# c50.net
KiCad netlist of a schematic drawn in EAGLE
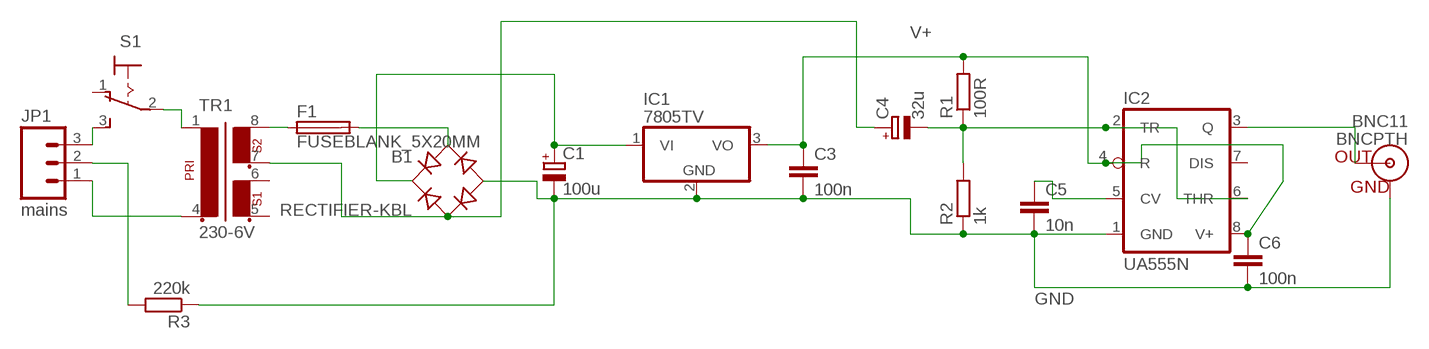
[diagram p0: schematic, sheet 1]

(export (version "E")
  (design (tool "Eeschema 10.0.6"))
  (components
    (comp (ref "B1")
      (value "RECTIFIER-KBL")
      (footprint "eagle-import:B-DIL")
      (libsource (lib "eagle-import") (part "B-DIL"))
    )
    (comp (ref "BNC11")
      (value "BNCPTH")
      (footprint "eagle-import:BNC")
      (libsource (lib "eagle-import") (part "BNCPTH"))
    )
    (comp (ref "C1")
      (value "100u")
      (footprint "eagle-import:E2,5-7")
      (libsource (lib "eagle-import") (part "CPOL-EUE2.5-7"))
    )
    (comp (ref "C3")
      (value "100n")
      (footprint "eagle-import:C050-024X044")
      (libsource (lib "eagle-import") (part "C-EU050-024X044"))
    )
    (comp (ref "C4")
      (value "32u")
      (footprint "eagle-import:E5-13")
      (libsource (lib "eagle-import") (part "CPOL-EUE5-13"))
    )
    (comp (ref "C5")
      (value "10n")
      (footprint "eagle-import:C050-024X044")
      (libsource (lib "eagle-import") (part "C-EU050-024X044"))
    )
    (comp (ref "C6")
      (value "100n")
      (footprint "eagle-import:C050-024X044")
      (libsource (lib "eagle-import") (part "C-EU050-024X044"))
    )
    (comp (ref "F1")
      (value "FUSEBLANK_5X20MM")
      (footprint "eagle-import:FUSE_HOLDER_5X20MM")
      (libsource (lib "eagle-import") (part "FUSEBLANK_5X20MM"))
    )
    (comp (ref "IC1")
      (value "7805TV")
      (footprint "eagle-import:TO220V")
      (libsource (lib "eagle-import") (part "78TV05"))
    )
    (comp (ref "IC2")
      (value "UA555N")
      (footprint "eagle-import:DIL08")
      (libsource (lib "eagle-import") (part "555NUA"))
    )
    (comp (ref "JP1")
      (value "mains")
      (footprint "eagle-import:SCREWTERMINAL-5MM-3")
      (libsource (lib "eagle-import") (part "M03-SCREW-5MM"))
    )
    (comp (ref "R1")
      (value "100R")
      (footprint "eagle-import:0207_10")
      (libsource (lib "eagle-import") (part "R-EU_0207/10"))
    )
    (comp (ref "R2")
      (value "1k")
      (footprint "eagle-import:0207_10")
      (libsource (lib "eagle-import") (part "R-EU_0207/10"))
    )
    (comp (ref "R3")
      (value "220k")
      (footprint "eagle-import:0207_10")
      (libsource (lib "eagle-import") (part "R-EU_0207/10"))
    )
    (comp (ref "S1")
      (value "320-916")
      (footprint "eagle-import:320-916")
      (libsource (lib "eagle-import") (part "320-916"))
    )
    (comp (ref "TR1")
      (value "230-6V")
      (footprint "eagle-import:EE20-2")
      (libsource (lib "eagle-import") (part "EE20-2"))
    )
  )
  (nets
    (net (code "1") (name "/GND") (class "Default")
      (node (ref "B1") (pin "-") (pinfunction "-_-") (pintype "passive"))
      (node (ref "BNC11") (pin "GND") (pinfunction "GND_GND") (pintype "bidirectional"))
      (node (ref "C1") (pin "-") (pinfunction "-_-") (pintype "passive"))
      (node (ref "C3") (pin "2") (pinfunction "2_2") (pintype "passive"))
      (node (ref "C5") (pin "2") (pinfunction "2_2") (pintype "passive"))
      (node (ref "C6") (pin "2") (pinfunction "2_2") (pintype "passive"))
      (node (ref "IC1") (pin "2") (pinfunction "GND_2") (pintype "passive"))
      (node (ref "IC2") (pin "1") (pinfunction "GND_1") (pintype "power_in"))
      (node (ref "R2") (pin "1") (pinfunction "1_1") (pintype "passive"))
      (node (ref "R3") (pin "1") (pinfunction "1_1") (pintype "passive"))
    )
    (net (code "2") (name "/V+") (class "Default")
      (node (ref "C3") (pin "1") (pinfunction "1_1") (pintype "passive"))
      (node (ref "C6") (pin "1") (pinfunction "1_1") (pintype "passive"))
      (node (ref "IC1") (pin "3") (pinfunction "VO_3") (pintype "passive"))
      (node (ref "IC2") (pin "4") (pinfunction "R_4") (pintype "input"))
      (node (ref "IC2") (pin "8") (pinfunction "V+_8") (pintype "power_in"))
      (node (ref "R1") (pin "2") (pinfunction "2_2") (pintype "passive"))
    )
    (net (code "3") (name "Net-(B1-PadAC1)") (class "Default")
      (node (ref "B1") (pin "AC1") (pinfunction "AC1_AC1") (pintype "passive"))
      (node (ref "F1") (pin "2") (pinfunction "2_2") (pintype "passive"))
    )
    (net (code "4") (name "Net-(BNC11-OUT)") (class "Default")
      (node (ref "BNC11") (pin "S") (pinfunction "OUT_S") (pintype "bidirectional"))
      (node (ref "IC2") (pin "3") (pinfunction "Q_3") (pintype "output"))
    )
    (net (code "5") (name "Net-(IC1-VI)") (class "Default")
      (node (ref "B1") (pin "+") (pinfunction "+_+") (pintype "passive"))
      (node (ref "C1") (pin "+") (pinfunction "+_+") (pintype "passive"))
      (node (ref "IC1") (pin "1") (pinfunction "VI_1") (pintype "input"))
    )
    (net (code "6") (name "Net-(IC2-CV)") (class "Default")
      (node (ref "C5") (pin "1") (pinfunction "1_1") (pintype "passive"))
      (node (ref "IC2") (pin "5") (pinfunction "CV_5") (pintype "input"))
    )
    (net (code "7") (name "Net-(IC2-THR)") (class "Default")
      (node (ref "C4") (pin "-") (pinfunction "-_-") (pintype "passive"))
      (node (ref "IC2") (pin "2") (pinfunction "TR_2") (pintype "input"))
      (node (ref "IC2") (pin "6") (pinfunction "THR_6") (pintype "input"))
      (node (ref "R1") (pin "1") (pinfunction "1_1") (pintype "passive"))
      (node (ref "R2") (pin "2") (pinfunction "2_2") (pintype "passive"))
    )
    (net (code "8") (name "Net-(JP1-Pad2)") (class "Default")
      (node (ref "JP1") (pin "2") (pinfunction "2_2") (pintype "passive"))
      (node (ref "R3") (pin "2") (pinfunction "2_2") (pintype "passive"))
    )
    (net (code "9") (name "Net-(S1-P)") (class "Default")
      (node (ref "S1") (pin "2") (pinfunction "P_2") (pintype "passive"))
      (node (ref "TR1") (pin "1") (pinfunction "1_1") (pintype "passive"))
    )
    (net (code "10") (name "Net-(S1-S)") (class "Default")
      (node (ref "JP1") (pin "3") (pinfunction "3_3") (pintype "passive"))
      (node (ref "S1") (pin "3") (pinfunction "S_3") (pintype "passive"))
    )
    (net (code "11") (name "Net-(TR1-2)") (class "Default")
      (node (ref "JP1") (pin "1") (pinfunction "1_1") (pintype "passive"))
      (node (ref "TR1") (pin "4") (pinfunction "2_4") (pintype "passive"))
    )
    (net (code "12") (name "Net-(TR1-5)") (class "Default")
      (node (ref "B1") (pin "AC2") (pinfunction "AC2_AC2") (pintype "passive"))
      (node (ref "C4") (pin "+") (pinfunction "+_+") (pintype "passive"))
      (node (ref "TR1") (pin "7") (pinfunction "5_7") (pintype "passive"))
    )
    (net (code "13") (name "Net-(TR1-6)") (class "Default")
      (node (ref "F1") (pin "1") (pinfunction "1_1") (pintype "passive"))
      (node (ref "TR1") (pin "8") (pinfunction "6_8") (pintype "passive"))
    )
    (net (code "14") (name "unconnected-(IC2-DIS-Pad7)") (class "Default")
      (node (ref "IC2") (pin "7") (pinfunction "DIS_7") (pintype "input"))
    )
    (net (code "15") (name "unconnected-(S1-O-Pad1)") (class "Default")
      (node (ref "S1") (pin "1") (pinfunction "O_1") (pintype "passive"))
    )
    (net (code "16") (name "unconnected-(TR1-3-Pad5)") (class "Default")
      (node (ref "TR1") (pin "5") (pinfunction "3_5") (pintype "passive"))
    )
    (net (code "17") (name "unconnected-(TR1-4-Pad6)") (class "Default")
      (node (ref "TR1") (pin "6") (pinfunction "4_6") (pintype "passive"))
    )
  )
)
